# OpAmpSCH.net
KiCad netlist of a schematic drawn in Altium Designer
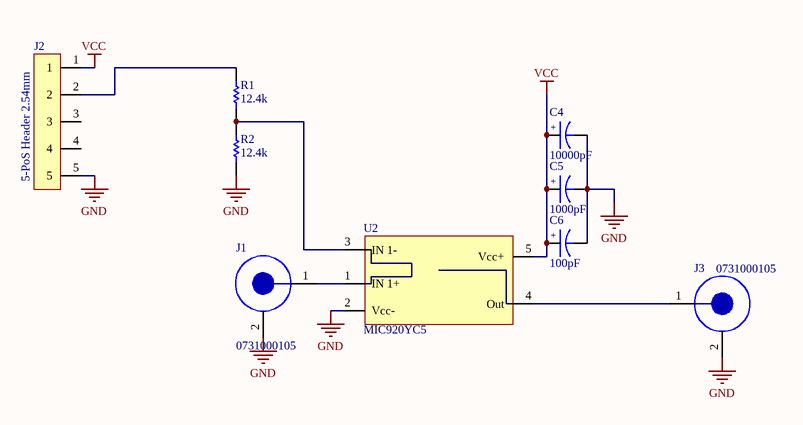
[diagram p0: OpAmpSCH.SchDoc]

(export (version "E")
  (design (tool "Eeschema 10.0.6"))
  (components
    (comp (ref "C4")
      (value "10000pF")
      (footprint "0603C")
      (description "Cap Poly")
      (libsource (lib "GENERIC_LIB") (part "CPoly"))
    )
    (comp (ref "C5")
      (value "1000pF")
      (footprint "0603C")
      (description "Cap Poly")
      (libsource (lib "GENERIC_LIB") (part "CPoly"))
    )
    (comp (ref "C6")
      (value "100pF")
      (footprint "0603C")
      (description "Cap Poly")
      (libsource (lib "GENERIC_LIB") (part "CPoly"))
    )
    (comp (ref "J1")
      (value "0731000105")
      (footprint "0731000105")
      (description "BNC Connector Jack, Female Socket 50Ohm Through Hole, Right Angle Solder")
      (libsource (lib "CON_LIB") (part "0731000105"))
    )
    (comp (ref "J2")
      (value "5-PoS Header 2.54mm")
      (footprint "2.54mm Pitch Header")
      (libsource (lib "CON_LIB") (part "5-PoS Header 2.54mm"))
    )
    (comp (ref "J3")
      (value "0731000105")
      (footprint "0731000105")
      (description "BNC Connector Jack, Female Socket 50Ohm Through Hole, Right Angle Solder")
      (libsource (lib "CON_LIB") (part "0731000105"))
    )
    (comp (ref "R1")
      (value "12.4k")
      (footprint "0603C")
      (description "Resistor")
      (fields (field (name "TOLERANCE") "5%"))
      (libsource (lib "GENERIC_LIB") (part "R"))
    )
    (comp (ref "R2")
      (value "12.4k")
      (footprint "0603C")
      (description "Resistor")
      (fields (field (name "TOLERANCE") "5%"))
      (libsource (lib "GENERIC_LIB") (part "R"))
    )
    (comp (ref "U2")
      (value "MIC920YC5")
      (footprint "MIC920")
      (description "General Purpose Amplifier 1 Circuit SC-70-5")
      (libsource (lib "ANALOG_LIB") (part "MIC920YC5-TR"))
    )
  )
  (nets
    (net (code "1") (name "GND") (class "Default")
      (node (ref "C4") (pin "2") (pinfunction "2_2") (pintype "passive"))
      (node (ref "C5") (pin "2") (pinfunction "2_2") (pintype "passive"))
      (node (ref "C6") (pin "2") (pinfunction "2_2") (pintype "passive"))
      (node (ref "J1") (pin "2") (pinfunction "2_2") (pintype "passive"))
      (node (ref "J2") (pin "5") (pinfunction "5_5") (pintype "passive"))
      (node (ref "J3") (pin "2") (pinfunction "2_2") (pintype "passive"))
      (node (ref "R2") (pin "1") (pinfunction "1_1") (pintype "passive"))
      (node (ref "U2") (pin "2") (pinfunction "Vcc-_2") (pintype "passive"))
    )
    (net (code "2") (name "Net-(J2-Pad2)") (class "Default")
      (node (ref "J2") (pin "2") (pinfunction "2_2") (pintype "passive"))
      (node (ref "R1") (pin "2") (pinfunction "2_2") (pintype "passive"))
    )
    (net (code "3") (name "Net-(U2-IN_1+)") (class "Default")
      (node (ref "J1") (pin "1") (pinfunction "1_1") (pintype "passive"))
      (node (ref "U2") (pin "1") (pinfunction "IN_1+_1") (pintype "passive"))
    )
    (net (code "4") (name "Net-(U2-IN_1-)") (class "Default")
      (node (ref "R1") (pin "1") (pinfunction "1_1") (pintype "passive"))
      (node (ref "R2") (pin "2") (pinfunction "2_2") (pintype "passive"))
      (node (ref "U2") (pin "3") (pinfunction "IN_1-_3") (pintype "passive"))
    )
    (net (code "5") (name "Net-(U2-Out)") (class "Default")
      (node (ref "J3") (pin "1") (pinfunction "1_1") (pintype "passive"))
      (node (ref "U2") (pin "4") (pinfunction "Out_4") (pintype "passive"))
    )
    (net (code "6") (name "VCC") (class "Default")
      (node (ref "C4") (pin "1") (pinfunction "1_1") (pintype "passive"))
      (node (ref "C5") (pin "1") (pinfunction "1_1") (pintype "passive"))
      (node (ref "C6") (pin "1") (pinfunction "1_1") (pintype "passive"))
      (node (ref "J2") (pin "1") (pinfunction "1_1") (pintype "passive"))
      (node (ref "U2") (pin "5") (pinfunction "Vcc+_5") (pintype "passive"))
    )
    (net (code "7") (name "unconnected-(J2-Pad3)") (class "Default")
      (node (ref "J2") (pin "3") (pinfunction "3_3") (pintype "passive"))
    )
    (net (code "8") (name "unconnected-(J2-Pad4)") (class "Default")
      (node (ref "J2") (pin "4") (pinfunction "4_4") (pintype "passive"))
    )
  )
)
